# DRV8301_Sense.net
KiCad netlist of a schematic drawn in Altium Designer
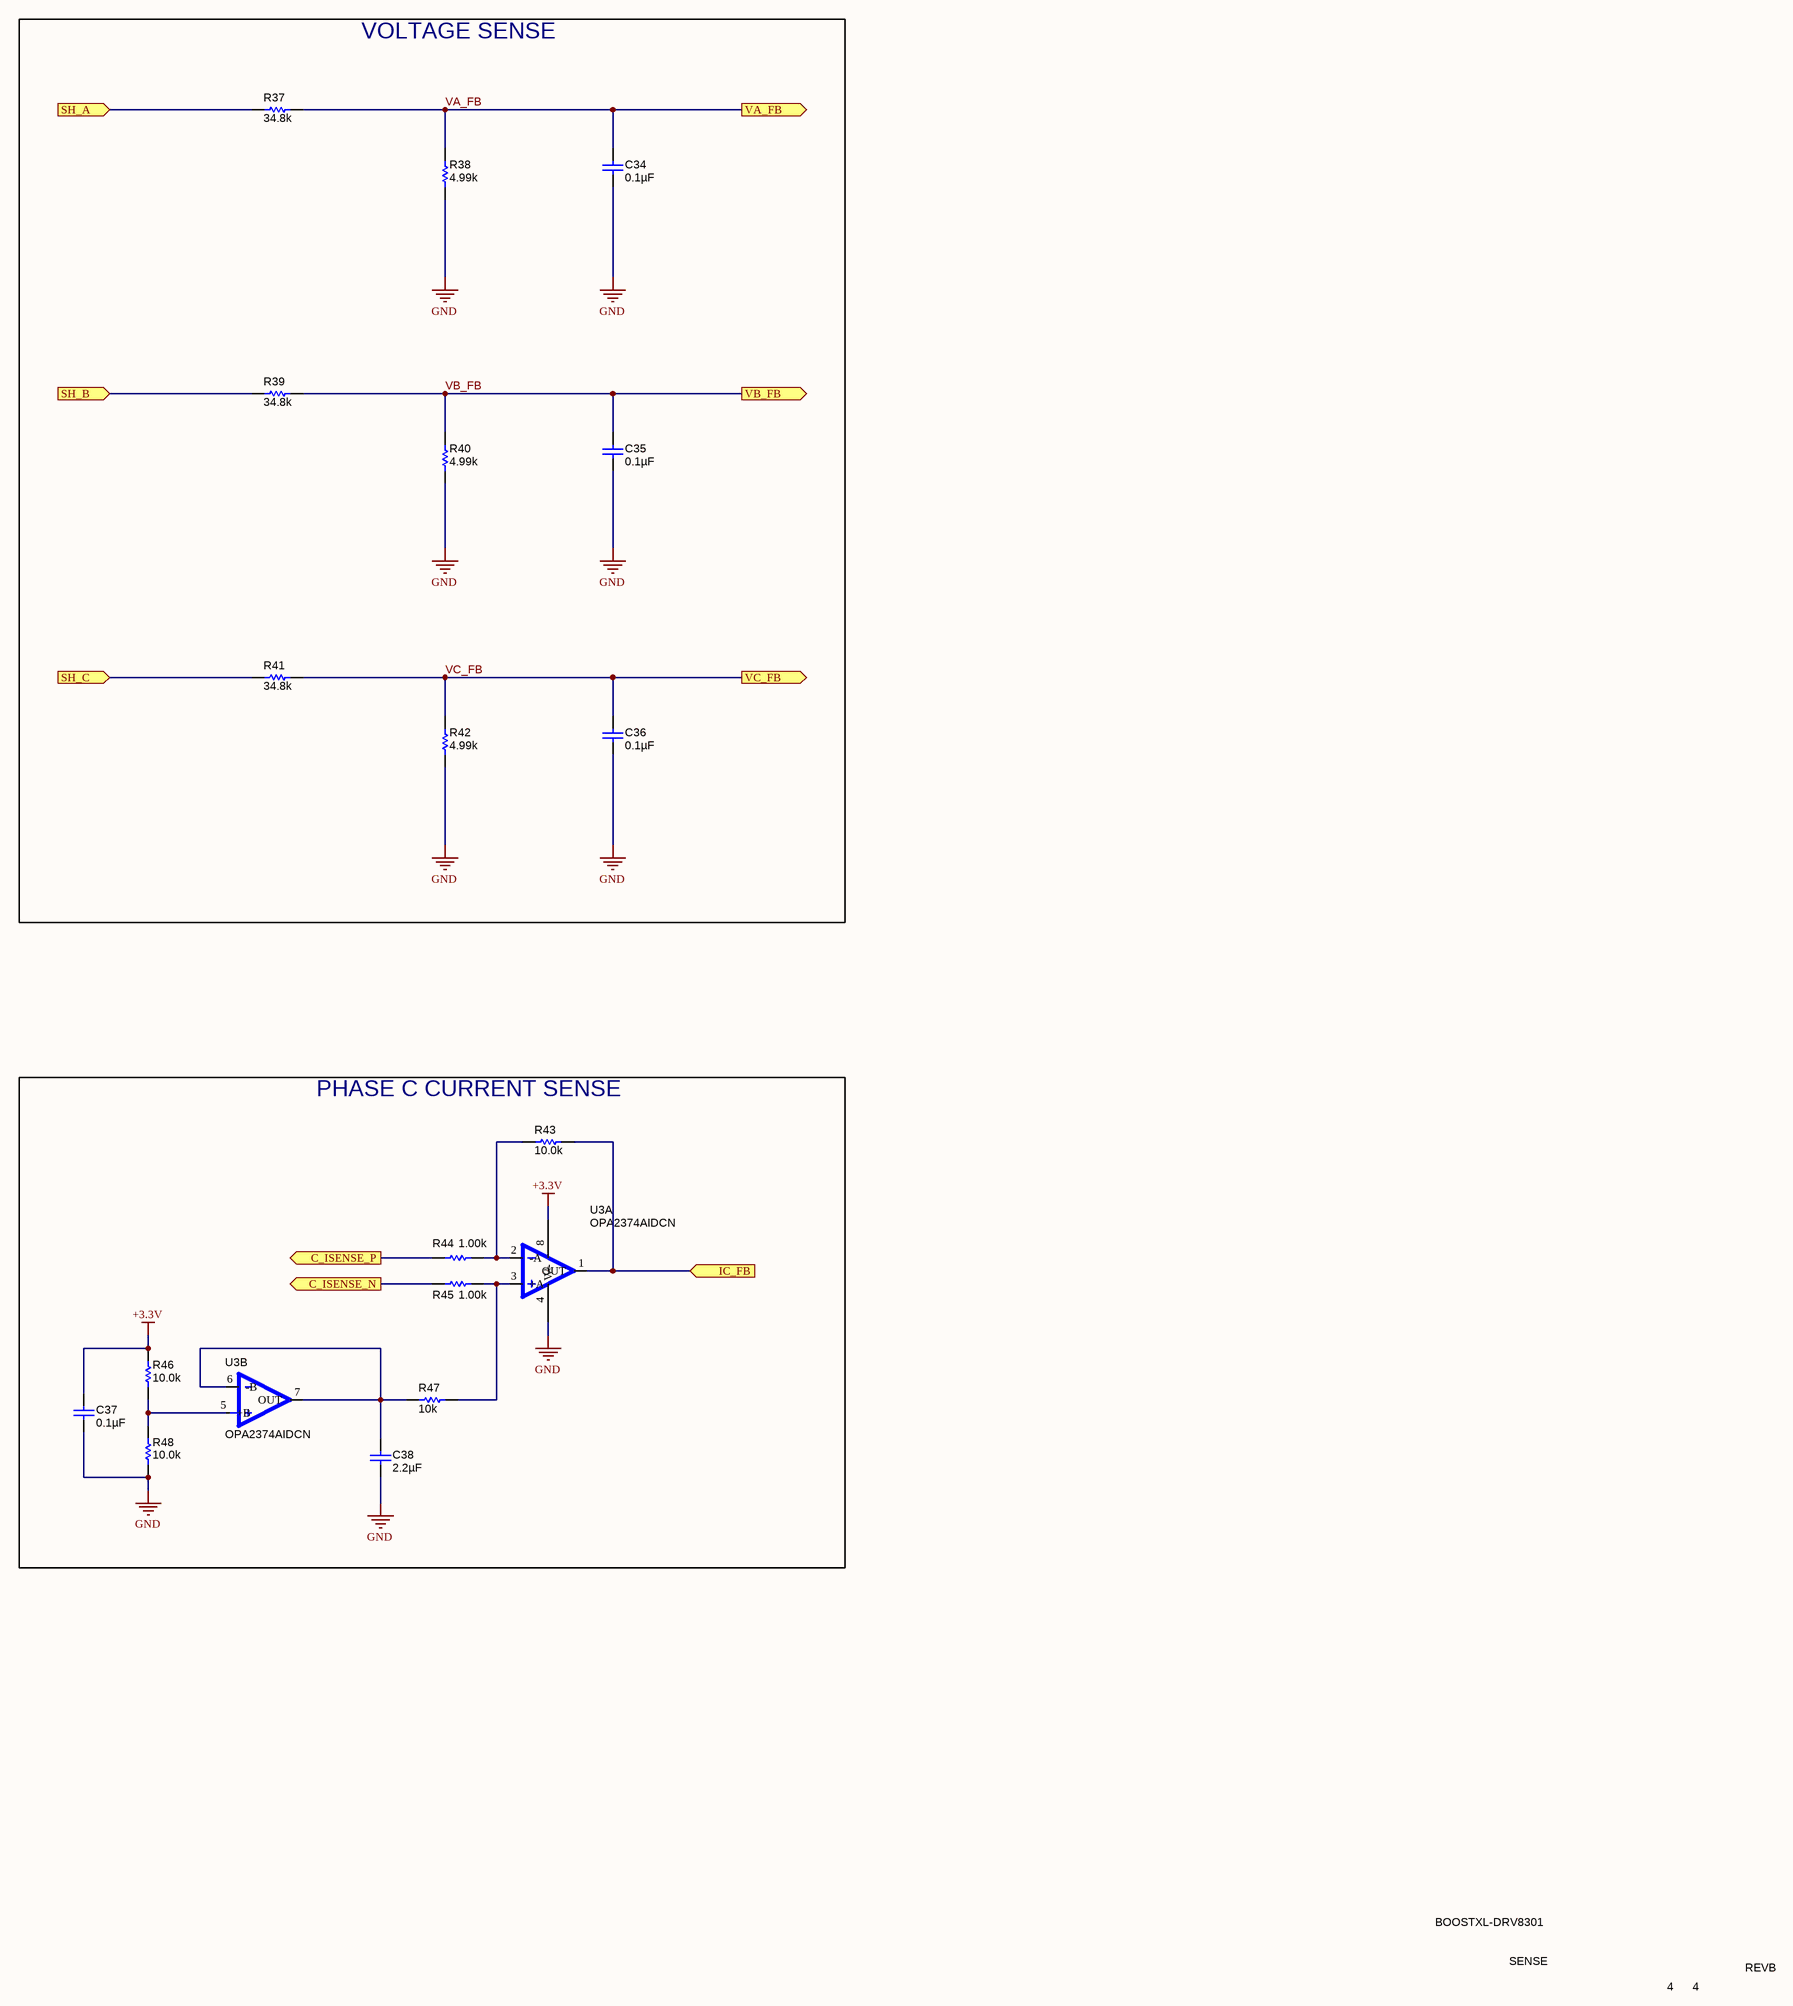
[diagram p0: DRV8301_Sense.SchDoc]

(export (version "E")
  (design (tool "Eeschema 10.0.6"))
  (components
    (comp (ref "C34")
      (value "C0603C104J4RACTU")
      (footprint "0603L")
      (description "CAP, CERM, 0.1uF, 16V, +/-5%, X7R, 0603")
      (fields
        (field (name "VALUEDISPLAYED") "0.1µF")
        (field (name "MANUFACTURER") "Kemet")
        (field (name "PUBLISHER") "Texas Instruments")
      )
      (libsource (lib "Capacitor_Ceramic") (part "C0603C104J4RACTU"))
    )
    (comp (ref "C35")
      (value "C0603C104J4RACTU")
      (footprint "0603L")
      (description "CAP, CERM, 0.1uF, 16V, +/-5%, X7R, 0603")
      (fields
        (field (name "VALUEDISPLAYED") "0.1µF")
        (field (name "MANUFACTURER") "Kemet")
        (field (name "PUBLISHER") "Texas Instruments")
      )
      (libsource (lib "Capacitor_Ceramic") (part "C0603C104J4RACTU"))
    )
    (comp (ref "C36")
      (value "C0603C104J4RACTU")
      (footprint "0603L")
      (description "CAP, CERM, 0.1uF, 16V, +/-5%, X7R, 0603")
      (fields
        (field (name "VALUEDISPLAYED") "0.1µF")
        (field (name "MANUFACTURER") "Kemet")
        (field (name "PUBLISHER") "Texas Instruments")
      )
      (libsource (lib "Capacitor_Ceramic") (part "C0603C104J4RACTU"))
    )
    (comp (ref "C37")
      (value "C0603C104J4RACTU")
      (footprint "0603L")
      (description "CAP, CERM, 0.1uF, 16V, +/-5%, X7R, 0603")
      (fields
        (field (name "VALUEDISPLAYED") "0.1µF")
        (field (name "MANUFACTURER") "Kemet")
        (field (name "PUBLISHER") "Texas Instruments")
      )
      (libsource (lib "Capacitor_Ceramic") (part "C0603C104J4RACTU"))
    )
    (comp (ref "C38")
      (value "C0603C225M8PACTU")
      (footprint "0603L")
      (description "CAP, CERM, 2.2uF, 10V, +/-20%, X5R, 0603")
      (fields
        (field (name "VALUEDISPLAYED") "2.2µF")
        (field (name "MANUFACTURER") "Kemet")
        (field (name "PUBLISHER") "Texas Instruments")
      )
      (libsource (lib "Capacitor_Ceramic") (part "C0603C225M8PACTU"))
    )
    (comp (ref "R37")
      (value "34.8k")
      (footprint "0603L")
      (description "RES, 34.8k ohm, 1%, 0.1W, 0603")
      (fields
        (field (name "PARTNUMBER") "CRCW060334K8FKEA")
        (field (name "MANUFACTURER") "Vishay-Dale")
        (field (name "PUBLISHER") "Texas Instruments")
      )
      (libsource (lib "Resistor_0603") (part "CRCW060334K8FKEA"))
    )
    (comp (ref "R38")
      (value "4.99k")
      (footprint "0603L")
      (description "RES, 4.99k ohm, 1%, 0.1W, 0603")
      (fields
        (field (name "PARTNUMBER") "CRCW06034K99FKEA")
        (field (name "MANUFACTURER") "Vishay-Dale")
        (field (name "PUBLISHER") "Texas Instruments")
      )
      (libsource (lib "Resistor_0603") (part "CRCW06034K99FKEA"))
    )
    (comp (ref "R39")
      (value "34.8k")
      (footprint "0603L")
      (description "RES, 34.8k ohm, 1%, 0.1W, 0603")
      (fields
        (field (name "PARTNUMBER") "CRCW060334K8FKEA")
        (field (name "MANUFACTURER") "Vishay-Dale")
        (field (name "PUBLISHER") "Texas Instruments")
      )
      (libsource (lib "Resistor_0603") (part "CRCW060334K8FKEA"))
    )
    (comp (ref "R40")
      (value "4.99k")
      (footprint "0603L")
      (description "RES, 4.99k ohm, 1%, 0.1W, 0603")
      (fields
        (field (name "PARTNUMBER") "CRCW06034K99FKEA")
        (field (name "MANUFACTURER") "Vishay-Dale")
        (field (name "PUBLISHER") "Texas Instruments")
      )
      (libsource (lib "Resistor_0603") (part "CRCW06034K99FKEA"))
    )
    (comp (ref "R41")
      (value "34.8k")
      (footprint "0603L")
      (description "RES, 34.8k ohm, 1%, 0.1W, 0603")
      (fields
        (field (name "PARTNUMBER") "CRCW060334K8FKEA")
        (field (name "MANUFACTURER") "Vishay-Dale")
        (field (name "PUBLISHER") "Texas Instruments")
      )
      (libsource (lib "Resistor_0603") (part "CRCW060334K8FKEA"))
    )
    (comp (ref "R42")
      (value "4.99k")
      (footprint "0603L")
      (description "RES, 4.99k ohm, 1%, 0.1W, 0603")
      (fields
        (field (name "PARTNUMBER") "CRCW06034K99FKEA")
        (field (name "MANUFACTURER") "Vishay-Dale")
        (field (name "PUBLISHER") "Texas Instruments")
      )
      (libsource (lib "Resistor_0603") (part "CRCW06034K99FKEA"))
    )
    (comp (ref "R43")
      (value "10.0k")
      (footprint "0603L")
      (description "RES, 10.0k ohm, 0.1%, 0.1W, 0603")
      (fields
        (field (name "PARTNUMBER") "RG1608P-103-B-T5")
        (field (name "MANUFACTURER") "Susumu Co Ltd")
        (field (name "PUBLISHER") "Texas Instruments")
      )
      (libsource (lib "Resistor_0603") (part "RG1608P-103-B-T5"))
    )
    (comp (ref "R44")
      (value "1.00k")
      (footprint "0603L")
      (description "RES, 1.00k ohm, 1%, 0.1W, 0603")
      (fields
        (field (name "PARTNUMBER") "CRCW06031K00FKEA")
        (field (name "MANUFACTURER") "Vishay-Dale")
        (field (name "PUBLISHER") "Texas Instruments")
      )
      (libsource (lib "Resistor_0603") (part "CRCW06031K00FKEA"))
    )
    (comp (ref "R45")
      (value "1.00k")
      (footprint "0603L")
      (description "RES, 1.00k ohm, 1%, 0.1W, 0603")
      (fields
        (field (name "PARTNUMBER") "CRCW06031K00FKEA")
        (field (name "MANUFACTURER") "Vishay-Dale")
        (field (name "PUBLISHER") "Texas Instruments")
      )
      (libsource (lib "Resistor_0603") (part "CRCW06031K00FKEA"))
    )
    (comp (ref "R46")
      (value "10.0k")
      (footprint "0603L")
      (description "RES, 10.0k ohm, 0.1%, 0.1W, 0603")
      (fields
        (field (name "PARTNUMBER") "RG1608P-103-B-T5")
        (field (name "MANUFACTURER") "Susumu Co Ltd")
        (field (name "PUBLISHER") "Texas Instruments")
      )
      (libsource (lib "Resistor_0603") (part "RG1608P-103-B-T5"))
    )
    (comp (ref "R47")
      (value "10k")
      (footprint "0603L")
      (description "RES, 10k ohm, 5%, 0.1W, 0603")
      (fields
        (field (name "PARTNUMBER") "CRCW060310K0JNEA")
        (field (name "MANUFACTURER") "Vishay-Dale")
        (field (name "PUBLISHER") "Texas Instruments")
      )
      (libsource (lib "Resistor_0603") (part "CRCW060310K0JNEA"))
    )
    (comp (ref "R48")
      (value "10.0k")
      (footprint "0603L")
      (description "RES, 10.0k ohm, 0.1%, 0.1W, 0603")
      (fields
        (field (name "PARTNUMBER") "RG1608P-103-B-T5")
        (field (name "MANUFACTURER") "Susumu Co Ltd")
        (field (name "PUBLISHER") "Texas Instruments")
      )
      (libsource (lib "Resistor_0603") (part "RG1608P-103-B-T5"))
    )
    (comp (ref "U3")
      (value "OPA2374AIDCN")
      (footprint "DCN")
      (description "IC, CMOS, R-R I/O  Op Amp, Single Supply, 6.5MHz, 585uA")
      (fields (field (name "MANUFACTURER") "TI"))
      (libsource (lib "PADSlegacy_Active") (part "OPA2374AIDCN"))
    )
  )
  (nets
    (net (code "1") (name "+3.3V") (class "Default")
      (node (ref "C37") (pin "1") (pinfunction "1_1") (pintype "passive"))
      (node (ref "R46") (pin "2") (pinfunction "2_2") (pintype "passive"))
      (node (ref "U3") (pin "8") (pinfunction "V+_8") (pintype "passive"))
    )
    (net (code "2") (name "/C_ISENSE_N") (class "Default")
      (node (ref "R45") (pin "1") (pinfunction "1_1") (pintype "passive"))
    )
    (net (code "3") (name "/C_ISENSE_P") (class "Default")
      (node (ref "R44") (pin "1") (pinfunction "1_1") (pintype "passive"))
    )
    (net (code "4") (name "/IC_FB") (class "Default")
      (node (ref "R43") (pin "2") (pinfunction "2_2") (pintype "passive"))
      (node (ref "U3") (pin "1") (pinfunction "OUT_1") (pintype "passive"))
    )
    (net (code "5") (name "/SH_A") (class "Default")
      (node (ref "R37") (pin "1") (pinfunction "1_1") (pintype "passive"))
    )
    (net (code "6") (name "/SH_B") (class "Default")
      (node (ref "R39") (pin "1") (pinfunction "1_1") (pintype "passive"))
    )
    (net (code "7") (name "/SH_C") (class "Default")
      (node (ref "R41") (pin "1") (pinfunction "1_1") (pintype "passive"))
    )
    (net (code "8") (name "/VA_FB") (class "Default")
      (node (ref "C34") (pin "1") (pinfunction "1_1") (pintype "passive"))
      (node (ref "R37") (pin "2") (pinfunction "2_2") (pintype "passive"))
      (node (ref "R38") (pin "2") (pinfunction "2_2") (pintype "passive"))
    )
    (net (code "9") (name "/VB_FB") (class "Default")
      (node (ref "C35") (pin "1") (pinfunction "1_1") (pintype "passive"))
      (node (ref "R39") (pin "2") (pinfunction "2_2") (pintype "passive"))
      (node (ref "R40") (pin "2") (pinfunction "2_2") (pintype "passive"))
    )
    (net (code "10") (name "/VC_FB") (class "Default")
      (node (ref "C36") (pin "1") (pinfunction "1_1") (pintype "passive"))
      (node (ref "R41") (pin "2") (pinfunction "2_2") (pintype "passive"))
      (node (ref "R42") (pin "2") (pinfunction "2_2") (pintype "passive"))
    )
    (net (code "11") (name "GND") (class "Default")
      (node (ref "C34") (pin "2") (pinfunction "2_2") (pintype "passive"))
      (node (ref "C35") (pin "2") (pinfunction "2_2") (pintype "passive"))
      (node (ref "C36") (pin "2") (pinfunction "2_2") (pintype "passive"))
      (node (ref "C37") (pin "2") (pinfunction "2_2") (pintype "passive"))
      (node (ref "C38") (pin "2") (pinfunction "2_2") (pintype "passive"))
      (node (ref "R38") (pin "1") (pinfunction "1_1") (pintype "passive"))
      (node (ref "R40") (pin "1") (pinfunction "1_1") (pintype "passive"))
      (node (ref "R42") (pin "1") (pinfunction "1_1") (pintype "passive"))
      (node (ref "R48") (pin "1") (pinfunction "1_1") (pintype "passive"))
      (node (ref "U3") (pin "4") (pinfunction "V-_4") (pintype "passive"))
    )
    (net (code "12") (name "Net-(U3A-+A)") (class "Default")
      (node (ref "R45") (pin "2") (pinfunction "2_2") (pintype "passive"))
      (node (ref "R47") (pin "2") (pinfunction "2_2") (pintype "passive"))
      (node (ref "U3") (pin "3") (pinfunction "+A_3") (pintype "passive"))
    )
    (net (code "13") (name "Net-(U3A--A)") (class "Default")
      (node (ref "R43") (pin "1") (pinfunction "1_1") (pintype "passive"))
      (node (ref "R44") (pin "2") (pinfunction "2_2") (pintype "passive"))
      (node (ref "U3") (pin "2") (pinfunction "-A_2") (pintype "passive"))
    )
    (net (code "14") (name "Net-(U3B-+B)") (class "Default")
      (node (ref "R46") (pin "1") (pinfunction "1_1") (pintype "passive"))
      (node (ref "R48") (pin "2") (pinfunction "2_2") (pintype "passive"))
      (node (ref "U3") (pin "5") (pinfunction "+B_5") (pintype "passive"))
    )
    (net (code "15") (name "Net-(U3B--B)") (class "Default")
      (node (ref "C38") (pin "1") (pinfunction "1_1") (pintype "passive"))
      (node (ref "R47") (pin "1") (pinfunction "1_1") (pintype "passive"))
      (node (ref "U3") (pin "6") (pinfunction "-B_6") (pintype "passive"))
      (node (ref "U3") (pin "7") (pinfunction "OUT_7") (pintype "passive"))
    )
  )
)
